# ANEMOI_LOG.net
KiCad netlist of a schematic drawn in EAGLE
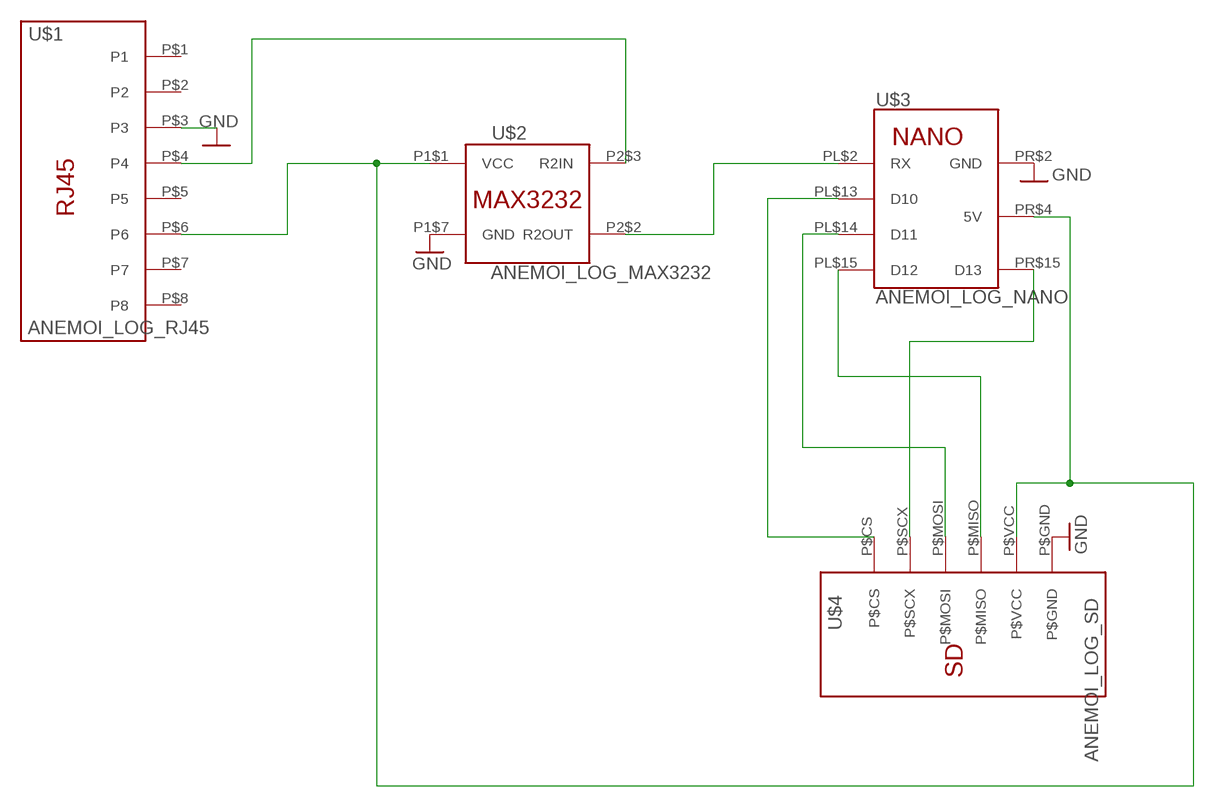
[diagram p0: schematic, sheet 1]

(export (version "E")
  (design (tool "Eeschema 10.0.6"))
  (components
    (comp (ref "U$1")
      (value "ANEMOI_LOG_RJ45")
      (footprint "eagle-import:ANEMOI_LOG_RJ45")
      (libsource (lib "eagle-import") (part "ANEMOI_LOG_RJ45"))
    )
    (comp (ref "U$2")
      (value "ANEMOI_LOG_MAX3232")
      (footprint "eagle-import:ANEMOI_LOG_MAX2323")
      (libsource (lib "eagle-import") (part "ANEMOI_LOG_MAX3232"))
    )
    (comp (ref "U$3")
      (value "ANEMOI_LOG_NANO")
      (footprint "eagle-import:ANEMOI_LOG_NANO")
      (libsource (lib "eagle-import") (part "ANEMOI_LOG_NANO"))
    )
    (comp (ref "U$4")
      (value "ANEMOI_LOG_SD")
      (footprint "eagle-import:ANEMOI_LOG_SD")
      (libsource (lib "eagle-import") (part "ANEMOI_LOG_SD"))
    )
  )
  (nets
    (net (code "1") (name "GND") (class "Default")
      (node (ref "U$1") (pin "P$3") (pinfunction "P3_P$3") (pintype "bidirectional"))
      (node (ref "U$2") (pin "P1$7") (pinfunction "GND_P1$7") (pintype "bidirectional"))
      (node (ref "U$3") (pin "PR$2") (pinfunction "GND_PR$2") (pintype "bidirectional"))
      (node (ref "U$4") (pin "P$GND") (pinfunction "P$GND_P$GND") (pintype "bidirectional"))
    )
    (net (code "2") (name "Net-(U$1-P4)") (class "Default")
      (node (ref "U$1") (pin "P$4") (pinfunction "P4_P$4") (pintype "bidirectional"))
      (node (ref "U$2") (pin "P2$3") (pinfunction "R2IN_P2$3") (pintype "bidirectional"))
    )
    (net (code "3") (name "Net-(U$1-P6)") (class "Default")
      (node (ref "U$1") (pin "P$6") (pinfunction "P6_P$6") (pintype "bidirectional"))
      (node (ref "U$2") (pin "P1$1") (pinfunction "VCC_P1$1") (pintype "bidirectional"))
      (node (ref "U$3") (pin "PR$4") (pinfunction "5V_PR$4") (pintype "bidirectional"))
      (node (ref "U$4") (pin "P$VCC") (pinfunction "P$VCC_P$VCC") (pintype "bidirectional"))
    )
    (net (code "4") (name "Net-(U$2-R2OUT)") (class "Default")
      (node (ref "U$2") (pin "P2$2") (pinfunction "R2OUT_P2$2") (pintype "bidirectional"))
      (node (ref "U$3") (pin "PL$2") (pinfunction "RX_PL$2") (pintype "bidirectional"))
    )
    (net (code "5") (name "Net-(U$3-D10)") (class "Default")
      (node (ref "U$3") (pin "PL$13") (pinfunction "D10_PL$13") (pintype "bidirectional"))
      (node (ref "U$4") (pin "P$CS") (pinfunction "P$CS_P$CS") (pintype "bidirectional"))
    )
    (net (code "6") (name "Net-(U$3-D11)") (class "Default")
      (node (ref "U$3") (pin "PL$14") (pinfunction "D11_PL$14") (pintype "bidirectional"))
      (node (ref "U$4") (pin "P$MOSI") (pinfunction "P$MOSI_P$MOSI") (pintype "bidirectional"))
    )
    (net (code "7") (name "Net-(U$3-D12)") (class "Default")
      (node (ref "U$3") (pin "PL$15") (pinfunction "D12_PL$15") (pintype "bidirectional"))
      (node (ref "U$4") (pin "P$MISO") (pinfunction "P$MISO_P$MISO") (pintype "bidirectional"))
    )
    (net (code "8") (name "Net-(U$3-D13)") (class "Default")
      (node (ref "U$3") (pin "PR$15") (pinfunction "D13_PR$15") (pintype "bidirectional"))
      (node (ref "U$4") (pin "P$SCX") (pinfunction "P$SCX_P$SCX") (pintype "bidirectional"))
    )
    (net (code "9") (name "unconnected-(U$1-P1-PadP$1)") (class "Default")
      (node (ref "U$1") (pin "P$1") (pinfunction "P1_P$1") (pintype "bidirectional"))
    )
    (net (code "10") (name "unconnected-(U$1-P2-PadP$2)") (class "Default")
      (node (ref "U$1") (pin "P$2") (pinfunction "P2_P$2") (pintype "bidirectional"))
    )
    (net (code "11") (name "unconnected-(U$1-P5-PadP$5)") (class "Default")
      (node (ref "U$1") (pin "P$5") (pinfunction "P5_P$5") (pintype "bidirectional"))
    )
    (net (code "12") (name "unconnected-(U$1-P7-PadP$7)") (class "Default")
      (node (ref "U$1") (pin "P$7") (pinfunction "P7_P$7") (pintype "bidirectional"))
    )
    (net (code "13") (name "unconnected-(U$1-P8-PadP$8)") (class "Default")
      (node (ref "U$1") (pin "P$8") (pinfunction "P8_P$8") (pintype "bidirectional"))
    )
  )
)
